# LEDSandButtons.net
KiCad netlist of a schematic drawn in Altium Designer
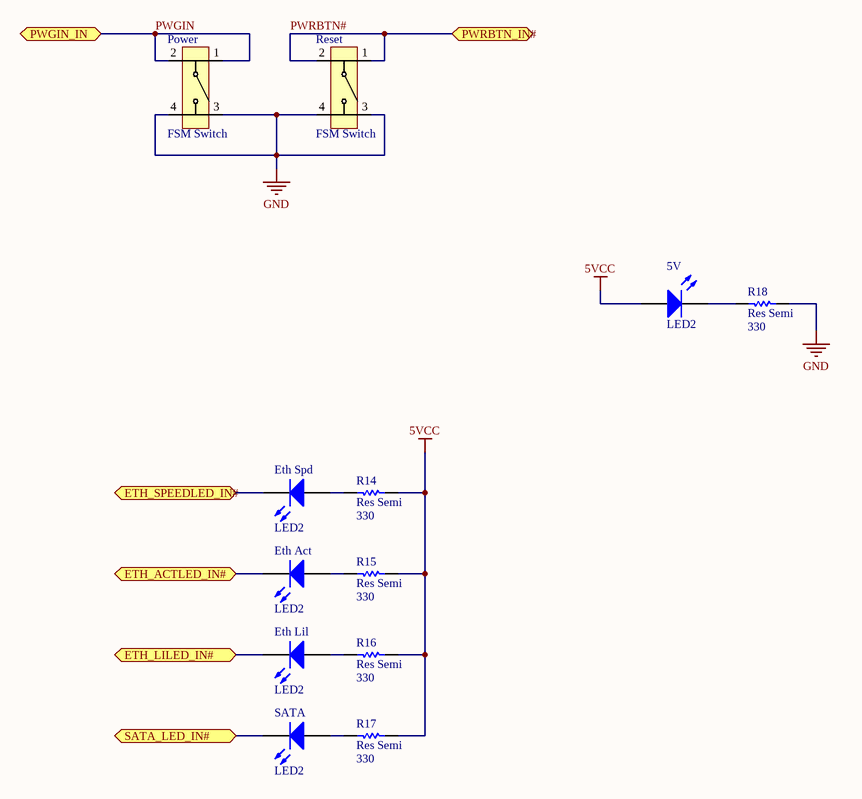
[diagram p0: LEDSandButtons.SchDoc]

(export (version "E")
  (design (tool "Eeschema 10.0.6"))
  (components
    (comp (ref "5V")
      (value "LED2")
      (footprint "C0805")
      (description "Typical RED, GREEN, YELLOW, AMBER GaAs LED")
      (fields (field (name "PUBLISHER") "Altium Limited"))
      (libsource (lib "Miscellaneous Devices") (part "LED2"))
    )
    (comp (ref "Eth Act")
      (value "LED2")
      (footprint "C0805")
      (description "Typical RED, GREEN, YELLOW, AMBER GaAs LED")
      (fields (field (name "PUBLISHER") "Altium Limited"))
      (libsource (lib "Miscellaneous Devices") (part "LED2"))
    )
    (comp (ref "Eth Lil")
      (value "LED2")
      (footprint "C0805")
      (description "Typical RED, GREEN, YELLOW, AMBER GaAs LED")
      (fields (field (name "PUBLISHER") "Altium Limited"))
      (libsource (lib "Miscellaneous Devices") (part "LED2"))
    )
    (comp (ref "Eth Spd")
      (value "LED2")
      (footprint "C0805")
      (description "Typical RED, GREEN, YELLOW, AMBER GaAs LED")
      (fields (field (name "PUBLISHER") "Altium Limited"))
      (libsource (lib "Miscellaneous Devices") (part "LED2"))
    )
    (comp (ref "Power")
      (value "FSM Switch")
      (footprint "Buttons:FSM4JH")
      (description "FSM 6mm Series Switch")
      (libsource (lib "Buttons") (part "FSM Switch"))
    )
    (comp (ref "R14")
      (value "Res Semi")
      (footprint "1005[0402]")
      (description "Semiconductor Resistor")
      (fields (field (name "ALTIUM_VALUE") "330") (field (name "PUBLISHER") "Altium Limited"))
      (libsource (lib "Miscellaneous Devices") (part "Res Semi"))
    )
    (comp (ref "R15")
      (value "Res Semi")
      (footprint "1005[0402]")
      (description "Semiconductor Resistor")
      (fields (field (name "ALTIUM_VALUE") "330") (field (name "PUBLISHER") "Altium Limited"))
      (libsource (lib "Miscellaneous Devices") (part "Res Semi"))
    )
    (comp (ref "R16")
      (value "Res Semi")
      (footprint "1005[0402]")
      (description "Semiconductor Resistor")
      (fields (field (name "ALTIUM_VALUE") "330") (field (name "PUBLISHER") "Altium Limited"))
      (libsource (lib "Miscellaneous Devices") (part "Res Semi"))
    )
    (comp (ref "R17")
      (value "Res Semi")
      (footprint "1005[0402]")
      (description "Semiconductor Resistor")
      (fields (field (name "ALTIUM_VALUE") "330") (field (name "PUBLISHER") "Altium Limited"))
      (libsource (lib "Miscellaneous Devices") (part "Res Semi"))
    )
    (comp (ref "R18")
      (value "Res Semi")
      (footprint "1005[0402]")
      (description "Semiconductor Resistor")
      (fields (field (name "ALTIUM_VALUE") "330") (field (name "PUBLISHER") "Altium Limited"))
      (libsource (lib "Miscellaneous Devices") (part "Res Semi"))
    )
    (comp (ref "Reset")
      (value "FSM Switch")
      (footprint "Buttons:FSM4JH")
      (description "FSM 6mm Series Switch")
      (libsource (lib "Buttons") (part "FSM Switch"))
    )
    (comp (ref "SATA")
      (value "LED2")
      (footprint "C0805")
      (description "Typical RED, GREEN, YELLOW, AMBER GaAs LED")
      (fields (field (name "PUBLISHER") "Altium Limited"))
      (libsource (lib "Miscellaneous Devices") (part "LED2"))
    )
  )
  (nets
    (net (code "1") (name "/ETH_ACTLED_IN#") (class "Default")
      (node (ref "Eth Act") (pin "2") (pinfunction "K_2") (pintype "passive"))
    )
    (net (code "2") (name "/ETH_LILED_IN#") (class "Default")
      (node (ref "Eth Lil") (pin "2") (pinfunction "K_2") (pintype "passive"))
    )
    (net (code "3") (name "/ETH_SPEEDLED_IN#") (class "Default")
      (node (ref "Eth Spd") (pin "2") (pinfunction "K_2") (pintype "passive"))
    )
    (net (code "4") (name "/PWGIN") (class "Default")
      (node (ref "Power") (pin "1") (pinfunction "1_1") (pintype "passive"))
      (node (ref "Power") (pin "2") (pinfunction "2_2") (pintype "passive"))
    )
    (net (code "5") (name "/PWRBTN#") (class "Default")
      (node (ref "Reset") (pin "1") (pinfunction "1_1") (pintype "passive"))
      (node (ref "Reset") (pin "2") (pinfunction "2_2") (pintype "passive"))
    )
    (net (code "6") (name "/SATA_LED_IN#") (class "Default")
      (node (ref "SATA") (pin "2") (pinfunction "K_2") (pintype "passive"))
    )
    (net (code "7") (name "5VCC") (class "Default")
      (node (ref "5V") (pin "1") (pinfunction "A_1") (pintype "passive"))
      (node (ref "R14") (pin "1") (pinfunction "1_1") (pintype "passive"))
      (node (ref "R15") (pin "1") (pinfunction "1_1") (pintype "passive"))
      (node (ref "R16") (pin "1") (pinfunction "1_1") (pintype "passive"))
      (node (ref "R17") (pin "1") (pinfunction "1_1") (pintype "passive"))
    )
    (net (code "8") (name "GND") (class "Default")
      (node (ref "Power") (pin "3") (pinfunction "3_3") (pintype "passive"))
      (node (ref "Power") (pin "4") (pinfunction "4_4") (pintype "passive"))
      (node (ref "R18") (pin "1") (pinfunction "1_1") (pintype "passive"))
      (node (ref "Reset") (pin "3") (pinfunction "3_3") (pintype "passive"))
      (node (ref "Reset") (pin "4") (pinfunction "4_4") (pintype "passive"))
    )
    (net (code "9") (name "Net-(5V-K)") (class "Default")
      (node (ref "5V") (pin "2") (pinfunction "K_2") (pintype "passive"))
      (node (ref "R18") (pin "2") (pinfunction "2_2") (pintype "passive"))
    )
    (net (code "10") (name "Net-(Eth Act-A)") (class "Default")
      (node (ref "Eth Act") (pin "1") (pinfunction "A_1") (pintype "passive"))
      (node (ref "R15") (pin "2") (pinfunction "2_2") (pintype "passive"))
    )
    (net (code "11") (name "Net-(Eth Lil-A)") (class "Default")
      (node (ref "Eth Lil") (pin "1") (pinfunction "A_1") (pintype "passive"))
      (node (ref "R16") (pin "2") (pinfunction "2_2") (pintype "passive"))
    )
    (net (code "12") (name "Net-(Eth Spd-A)") (class "Default")
      (node (ref "Eth Spd") (pin "1") (pinfunction "A_1") (pintype "passive"))
      (node (ref "R14") (pin "2") (pinfunction "2_2") (pintype "passive"))
    )
    (net (code "13") (name "Net-(SATA-A)") (class "Default")
      (node (ref "R17") (pin "2") (pinfunction "2_2") (pintype "passive"))
      (node (ref "SATA") (pin "1") (pinfunction "A_1") (pintype "passive"))
    )
  )
)
